# design.net
KiCad netlist of a schematic drawn in EAGLE
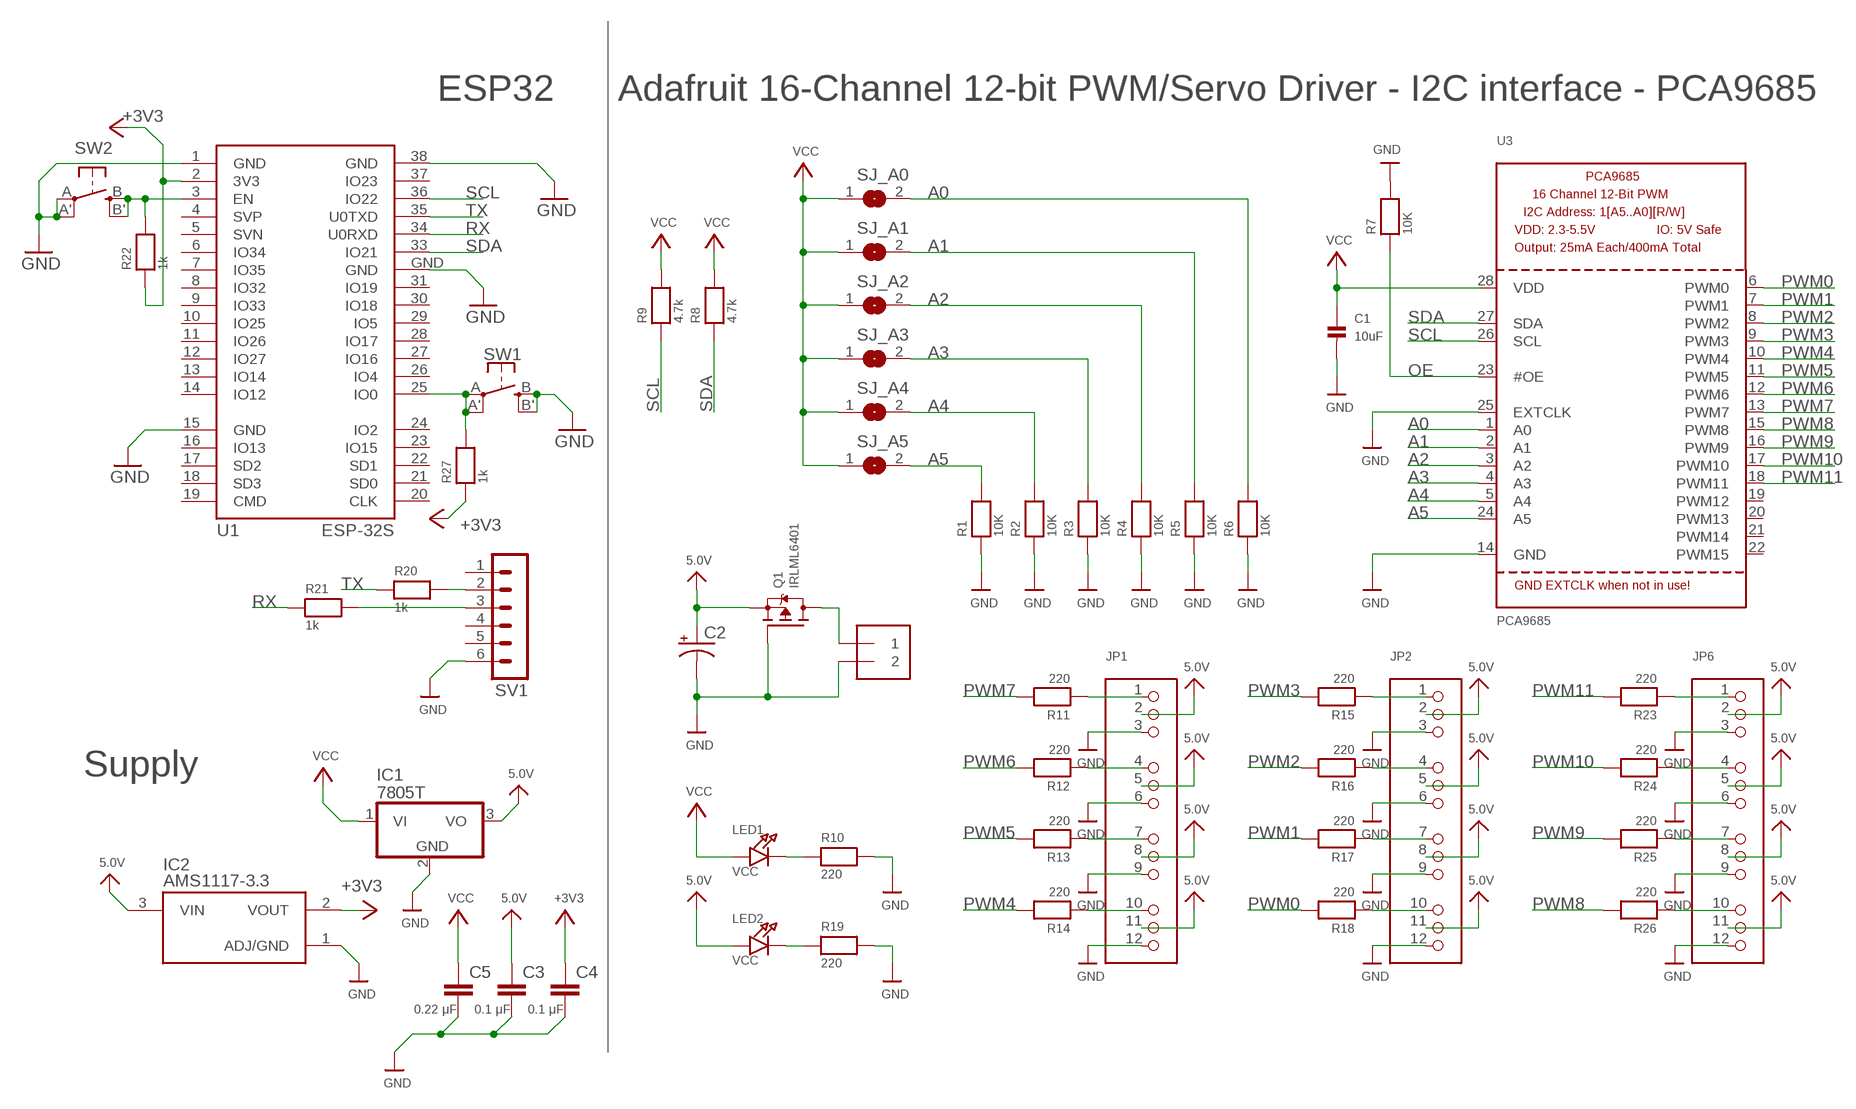
[diagram p0: schematic, sheet 1]

(export (version "E")
  (design (tool "Eeschema 10.0.6"))
  (components
    (comp (ref "C1")
      (value "10uF")
      (footprint "eagle-import:0805")
      (libsource (lib "eagle-import") (part "CAP_CERAMIC0805"))
    )
    (comp (ref "C2")
      (value "CPOL-USE3.5-8")
      (footprint "eagle-import:E3,5-8")
      (libsource (lib "eagle-import") (part "CPOL-USE3.5-8"))
    )
    (comp (ref "C3")
      (value "0.1 μF")
      (footprint "eagle-import:C2.5-2")
      (libsource (lib "eagle-import") (part "C2.5/2"))
    )
    (comp (ref "C4")
      (value "0.1 μF")
      (footprint "eagle-import:C2.5-2")
      (libsource (lib "eagle-import") (part "C2.5/2"))
    )
    (comp (ref "C5")
      (value "0.22 μF")
      (footprint "eagle-import:C2.5-2")
      (libsource (lib "eagle-import") (part "C2.5/2"))
    )
    (comp (ref "IC1")
      (value "7805T")
      (footprint "eagle-import:TO220H")
      (libsource (lib "eagle-import") (part "78T05"))
    )
    (comp (ref "IC2")
      (value "AMS1117-3.3")
      (footprint "eagle-import:SOT229P700X180-4N")
      (libsource (lib "eagle-import") (part "AMS1117-3.3"))
    )
    (comp (ref "J1")
      (value "TERMBLOCK_1X2-3.5MM")
      (footprint "eagle-import:1X2-3.5MM")
      (libsource (lib "eagle-import") (part "TERMBLOCK_1X2-3.5MM"))
    )
    (comp (ref "JP1")
      (value "HEADER-3X04")
      (footprint "eagle-import:3X04")
      (libsource (lib "eagle-import") (part "HEADER-3X04"))
    )
    (comp (ref "JP2")
      (value "HEADER-3X04")
      (footprint "eagle-import:3X04")
      (libsource (lib "eagle-import") (part "HEADER-3X04"))
    )
    (comp (ref "JP6")
      (value "HEADER-3X04")
      (footprint "eagle-import:3X04")
      (libsource (lib "eagle-import") (part "HEADER-3X04"))
    )
    (comp (ref "LED1")
      (value "VCC")
      (footprint "eagle-import:CHIPLED_0805")
      (libsource (lib "eagle-import") (part "LED0805"))
    )
    (comp (ref "LED2")
      (value "VCC")
      (footprint "eagle-import:CHIPLED_0805")
      (libsource (lib "eagle-import") (part "LED0805"))
    )
    (comp (ref "Q1")
      (value "IRLML6401")
      (footprint "eagle-import:SOT23-WIDE")
      (libsource (lib "eagle-import") (part "MOSFET-PWIDE"))
    )
    (comp (ref "R1")
      (value "10K")
      (footprint "eagle-import:0805")
      (libsource (lib "eagle-import") (part "RESISTOR0805"))
    )
    (comp (ref "R2")
      (value "10K")
      (footprint "eagle-import:0805")
      (libsource (lib "eagle-import") (part "RESISTOR0805"))
    )
    (comp (ref "R3")
      (value "10K")
      (footprint "eagle-import:0805")
      (libsource (lib "eagle-import") (part "RESISTOR0805"))
    )
    (comp (ref "R4")
      (value "10K")
      (footprint "eagle-import:0805")
      (libsource (lib "eagle-import") (part "RESISTOR0805"))
    )
    (comp (ref "R5")
      (value "10K")
      (footprint "eagle-import:0805")
      (libsource (lib "eagle-import") (part "RESISTOR0805"))
    )
    (comp (ref "R6")
      (value "10K")
      (footprint "eagle-import:0805")
      (libsource (lib "eagle-import") (part "RESISTOR0805"))
    )
    (comp (ref "R7")
      (value "10K")
      (footprint "eagle-import:0805")
      (libsource (lib "eagle-import") (part "RESISTOR0805"))
    )
    (comp (ref "R8")
      (value "4.7k")
      (footprint "eagle-import:0805")
      (libsource (lib "eagle-import") (part "RESISTOR0805"))
    )
    (comp (ref "R9")
      (value "4.7k")
      (footprint "eagle-import:0805")
      (libsource (lib "eagle-import") (part "RESISTOR0805"))
    )
    (comp (ref "R10")
      (value "220")
      (footprint "eagle-import:0805")
      (libsource (lib "eagle-import") (part "RESISTOR0805"))
    )
    (comp (ref "R11")
      (value "220")
      (footprint "eagle-import:0805")
      (libsource (lib "eagle-import") (part "RESISTOR0805"))
    )
    (comp (ref "R12")
      (value "220")
      (footprint "eagle-import:0805")
      (libsource (lib "eagle-import") (part "RESISTOR0805"))
    )
    (comp (ref "R13")
      (value "220")
      (footprint "eagle-import:0805")
      (libsource (lib "eagle-import") (part "RESISTOR0805"))
    )
    (comp (ref "R14")
      (value "220")
      (footprint "eagle-import:0805")
      (libsource (lib "eagle-import") (part "RESISTOR0805"))
    )
    (comp (ref "R15")
      (value "220")
      (footprint "eagle-import:0805")
      (libsource (lib "eagle-import") (part "RESISTOR0805"))
    )
    (comp (ref "R16")
      (value "220")
      (footprint "eagle-import:0805")
      (libsource (lib "eagle-import") (part "RESISTOR0805"))
    )
    (comp (ref "R17")
      (value "220")
      (footprint "eagle-import:0805")
      (libsource (lib "eagle-import") (part "RESISTOR0805"))
    )
    (comp (ref "R18")
      (value "220")
      (footprint "eagle-import:0805")
      (libsource (lib "eagle-import") (part "RESISTOR0805"))
    )
    (comp (ref "R19")
      (value "220")
      (footprint "eagle-import:0805")
      (libsource (lib "eagle-import") (part "RESISTOR0805"))
    )
    (comp (ref "R20")
      (value "1k")
      (footprint "eagle-import:0805")
      (libsource (lib "eagle-import") (part "RESISTOR0805"))
    )
    (comp (ref "R21")
      (value "1k")
      (footprint "eagle-import:0805")
      (libsource (lib "eagle-import") (part "RESISTOR0805"))
    )
    (comp (ref "R22")
      (value "1k")
      (footprint "eagle-import:0805")
      (libsource (lib "eagle-import") (part "RESISTOR0805"))
    )
    (comp (ref "R23")
      (value "220")
      (footprint "eagle-import:0805")
      (libsource (lib "eagle-import") (part "RESISTOR0805"))
    )
    (comp (ref "R24")
      (value "220")
      (footprint "eagle-import:0805")
      (libsource (lib "eagle-import") (part "RESISTOR0805"))
    )
    (comp (ref "R25")
      (value "220")
      (footprint "eagle-import:0805")
      (libsource (lib "eagle-import") (part "RESISTOR0805"))
    )
    (comp (ref "R26")
      (value "220")
      (footprint "eagle-import:0805")
      (libsource (lib "eagle-import") (part "RESISTOR0805"))
    )
    (comp (ref "R27")
      (value "1k")
      (footprint "eagle-import:0805")
      (libsource (lib "eagle-import") (part "RESISTOR0805"))
    )
    (comp (ref "SJ_A0")
      (value "SOLDERJUMPERREFLOW_NOPASTE")
      (footprint "eagle-import:SOLDERJUMPER_REFLOW_NOPASTE")
      (libsource (lib "eagle-import") (part "SOLDERJUMPERREFLOW_NOPASTE"))
    )
    (comp (ref "SJ_A1")
      (value "SOLDERJUMPERREFLOW_NOPASTE")
      (footprint "eagle-import:SOLDERJUMPER_REFLOW_NOPASTE")
      (libsource (lib "eagle-import") (part "SOLDERJUMPERREFLOW_NOPASTE"))
    )
    (comp (ref "SJ_A2")
      (value "SOLDERJUMPERREFLOW_NOPASTE")
      (footprint "eagle-import:SOLDERJUMPER_REFLOW_NOPASTE")
      (libsource (lib "eagle-import") (part "SOLDERJUMPERREFLOW_NOPASTE"))
    )
    (comp (ref "SJ_A3")
      (value "SOLDERJUMPERREFLOW_NOPASTE")
      (footprint "eagle-import:SOLDERJUMPER_REFLOW_NOPASTE")
      (libsource (lib "eagle-import") (part "SOLDERJUMPERREFLOW_NOPASTE"))
    )
    (comp (ref "SJ_A4")
      (value "SOLDERJUMPERREFLOW_NOPASTE")
      (footprint "eagle-import:SOLDERJUMPER_REFLOW_NOPASTE")
      (libsource (lib "eagle-import") (part "SOLDERJUMPERREFLOW_NOPASTE"))
    )
    (comp (ref "SJ_A5")
      (value "SOLDERJUMPERREFLOW_NOPASTE")
      (footprint "eagle-import:SOLDERJUMPER_REFLOW_NOPASTE")
      (libsource (lib "eagle-import") (part "SOLDERJUMPERREFLOW_NOPASTE"))
    )
    (comp (ref "SV1")
      (value "MA06-1")
      (footprint "eagle-import:MA06-1")
      (libsource (lib "eagle-import") (part "MA06-1"))
    )
    (comp (ref "SW1")
      (value "SPST_TACT-EVQQ2")
      (footprint "eagle-import:EVQ-Q2")
      (libsource (lib "eagle-import") (part "SPST_TACT-EVQQ2"))
    )
    (comp (ref "SW2")
      (value "SPST_TACT-EVQQ2")
      (footprint "eagle-import:EVQ-Q2")
      (libsource (lib "eagle-import") (part "SPST_TACT-EVQQ2"))
    )
    (comp (ref "U1")
      (value "ESP-32S")
      (footprint "eagle-import:ESP-32S")
      (libsource (lib "eagle-import") (part "ESP-32S"))
    )
    (comp (ref "U3")
      (value "PCA9685")
      (footprint "eagle-import:TSSOP28")
      (libsource (lib "eagle-import") (part "PCA9685"))
    )
  )
  (nets
    (net (code "1") (name "+3V3") (class "Default")
      (node (ref "C4") (pin "1") (pinfunction "1_1") (pintype "passive"))
      (node (ref "IC2") (pin "2") (pinfunction "VOUT_2") (pintype "output"))
      (node (ref "R22") (pin "1") (pinfunction "1_1") (pintype "passive"))
      (node (ref "R27") (pin "1") (pinfunction "1_1") (pintype "passive"))
      (node (ref "U1") (pin "2") (pinfunction "3V3_2") (pintype "power_in"))
    )
    (net (code "2") (name "/A0") (class "Default")
      (node (ref "R6") (pin "2") (pinfunction "2_2") (pintype "passive"))
      (node (ref "SJ_A0") (pin "2") (pinfunction "2_2") (pintype "passive"))
      (node (ref "U3") (pin "1") (pinfunction "A0_1") (pintype "bidirectional"))
    )
    (net (code "3") (name "/A1") (class "Default")
      (node (ref "R5") (pin "2") (pinfunction "2_2") (pintype "passive"))
      (node (ref "SJ_A1") (pin "2") (pinfunction "2_2") (pintype "passive"))
      (node (ref "U3") (pin "2") (pinfunction "A1_2") (pintype "bidirectional"))
    )
    (net (code "4") (name "/A2") (class "Default")
      (node (ref "R4") (pin "2") (pinfunction "2_2") (pintype "passive"))
      (node (ref "SJ_A2") (pin "2") (pinfunction "2_2") (pintype "passive"))
      (node (ref "U3") (pin "3") (pinfunction "A2_3") (pintype "bidirectional"))
    )
    (net (code "5") (name "/A3") (class "Default")
      (node (ref "R3") (pin "2") (pinfunction "2_2") (pintype "passive"))
      (node (ref "SJ_A3") (pin "2") (pinfunction "2_2") (pintype "passive"))
      (node (ref "U3") (pin "4") (pinfunction "A3_4") (pintype "bidirectional"))
    )
    (net (code "6") (name "/A4") (class "Default")
      (node (ref "R2") (pin "2") (pinfunction "2_2") (pintype "passive"))
      (node (ref "SJ_A4") (pin "2") (pinfunction "2_2") (pintype "passive"))
      (node (ref "U3") (pin "5") (pinfunction "A4_5") (pintype "bidirectional"))
    )
    (net (code "7") (name "/A5") (class "Default")
      (node (ref "R1") (pin "2") (pinfunction "2_2") (pintype "passive"))
      (node (ref "SJ_A5") (pin "2") (pinfunction "2_2") (pintype "passive"))
      (node (ref "U3") (pin "24") (pinfunction "A5_24") (pintype "bidirectional"))
    )
    (net (code "8") (name "/OE") (class "Default")
      (node (ref "R7") (pin "1") (pinfunction "1_1") (pintype "passive"))
      (node (ref "U3") (pin "23") (pinfunction "#OE_23") (pintype "input"))
    )
    (net (code "9") (name "/PWM0") (class "Default")
      (node (ref "R18") (pin "2") (pinfunction "2_2") (pintype "passive"))
      (node (ref "U3") (pin "6") (pinfunction "PWM0_6") (pintype "output"))
    )
    (net (code "10") (name "/PWM1") (class "Default")
      (node (ref "R17") (pin "2") (pinfunction "2_2") (pintype "passive"))
      (node (ref "U3") (pin "7") (pinfunction "PWM1_7") (pintype "output"))
    )
    (net (code "11") (name "/PWM2") (class "Default")
      (node (ref "R16") (pin "2") (pinfunction "2_2") (pintype "passive"))
      (node (ref "U3") (pin "8") (pinfunction "PWM2_8") (pintype "output"))
    )
    (net (code "12") (name "/PWM3") (class "Default")
      (node (ref "R15") (pin "2") (pinfunction "2_2") (pintype "passive"))
      (node (ref "U3") (pin "9") (pinfunction "PWM3_9") (pintype "output"))
    )
    (net (code "13") (name "/PWM4") (class "Default")
      (node (ref "R14") (pin "2") (pinfunction "2_2") (pintype "passive"))
      (node (ref "U3") (pin "10") (pinfunction "PWM4_10") (pintype "output"))
    )
    (net (code "14") (name "/PWM5") (class "Default")
      (node (ref "R13") (pin "2") (pinfunction "2_2") (pintype "passive"))
      (node (ref "U3") (pin "11") (pinfunction "PWM5_11") (pintype "output"))
    )
    (net (code "15") (name "/PWM6") (class "Default")
      (node (ref "R12") (pin "2") (pinfunction "2_2") (pintype "passive"))
      (node (ref "U3") (pin "12") (pinfunction "PWM6_12") (pintype "output"))
    )
    (net (code "16") (name "/PWM7") (class "Default")
      (node (ref "R11") (pin "2") (pinfunction "2_2") (pintype "passive"))
      (node (ref "U3") (pin "13") (pinfunction "PWM7_13") (pintype "output"))
    )
    (net (code "17") (name "/PWM8") (class "Default")
      (node (ref "R26") (pin "2") (pinfunction "2_2") (pintype "passive"))
      (node (ref "U3") (pin "15") (pinfunction "PWM8_15") (pintype "output"))
    )
    (net (code "18") (name "/PWM9") (class "Default")
      (node (ref "R25") (pin "2") (pinfunction "2_2") (pintype "passive"))
      (node (ref "U3") (pin "16") (pinfunction "PWM9_16") (pintype "output"))
    )
    (net (code "19") (name "/PWM10") (class "Default")
      (node (ref "R24") (pin "2") (pinfunction "2_2") (pintype "passive"))
      (node (ref "U3") (pin "17") (pinfunction "PWM10_17") (pintype "output"))
    )
    (net (code "20") (name "/PWM11") (class "Default")
      (node (ref "R23") (pin "2") (pinfunction "2_2") (pintype "passive"))
      (node (ref "U3") (pin "18") (pinfunction "PWM11_18") (pintype "output"))
    )
    (net (code "21") (name "/RX") (class "Default")
      (node (ref "R21") (pin "1") (pinfunction "1_1") (pintype "passive"))
      (node (ref "U1") (pin "34") (pinfunction "U0RXD_34") (pintype "bidirectional"))
    )
    (net (code "22") (name "/SCL") (class "Default")
      (node (ref "R9") (pin "1") (pinfunction "1_1") (pintype "passive"))
      (node (ref "U1") (pin "36") (pinfunction "IO22_36") (pintype "bidirectional"))
      (node (ref "U3") (pin "26") (pinfunction "SCL_26") (pintype "bidirectional"))
    )
    (net (code "23") (name "/SDA") (class "Default")
      (node (ref "R8") (pin "1") (pinfunction "1_1") (pintype "passive"))
      (node (ref "U1") (pin "33") (pinfunction "IO21_33") (pintype "bidirectional"))
      (node (ref "U3") (pin "27") (pinfunction "SDA_27") (pintype "bidirectional"))
    )
    (net (code "24") (name "/TX") (class "Default")
      (node (ref "R20") (pin "1") (pinfunction "1_1") (pintype "passive"))
      (node (ref "U1") (pin "35") (pinfunction "U0TXD_35") (pintype "bidirectional"))
    )
    (net (code "25") (name "5.0V") (class "Default")
      (node (ref "C2") (pin "+") (pinfunction "+_+") (pintype "passive"))
      (node (ref "C3") (pin "1") (pinfunction "1_1") (pintype "passive"))
      (node (ref "IC1") (pin "3") (pinfunction "VO_3") (pintype "passive"))
      (node (ref "IC2") (pin "3") (pinfunction "VIN_3") (pintype "input"))
      (node (ref "JP1") (pin "11") (pinfunction "11_11") (pintype "passive"))
      (node (ref "JP1") (pin "2") (pinfunction "2_2") (pintype "passive"))
      (node (ref "JP1") (pin "5") (pinfunction "5_5") (pintype "passive"))
      (node (ref "JP1") (pin "8") (pinfunction "8_8") (pintype "passive"))
      (node (ref "JP2") (pin "11") (pinfunction "11_11") (pintype "passive"))
      (node (ref "JP2") (pin "2") (pinfunction "2_2") (pintype "passive"))
      (node (ref "JP2") (pin "5") (pinfunction "5_5") (pintype "passive"))
      (node (ref "JP2") (pin "8") (pinfunction "8_8") (pintype "passive"))
      (node (ref "JP6") (pin "11") (pinfunction "11_11") (pintype "passive"))
      (node (ref "JP6") (pin "2") (pinfunction "2_2") (pintype "passive"))
      (node (ref "JP6") (pin "5") (pinfunction "5_5") (pintype "passive"))
      (node (ref "JP6") (pin "8") (pinfunction "8_8") (pintype "passive"))
      (node (ref "LED2") (pin "A") (pinfunction "A_A") (pintype "passive"))
      (node (ref "Q1") (pin "2") (pinfunction "S_2") (pintype "passive"))
    )
    (net (code "26") (name "GND") (class "Default")
      (node (ref "C1") (pin "2") (pinfunction "P$2_2") (pintype "passive"))
      (node (ref "C2") (pin "-") (pinfunction "-_-") (pintype "passive"))
      (node (ref "C3") (pin "2") (pinfunction "2_2") (pintype "passive"))
      (node (ref "C4") (pin "2") (pinfunction "2_2") (pintype "passive"))
      (node (ref "C5") (pin "2") (pinfunction "2_2") (pintype "passive"))
      (node (ref "IC1") (pin "2") (pinfunction "GND_2") (pintype "passive"))
      (node (ref "IC2") (pin "1") (pinfunction "ADJ/GND_1") (pintype "power_in"))
      (node (ref "J1") (pin "2") (pinfunction "2_2") (pintype "passive"))
      (node (ref "JP1") (pin "12") (pinfunction "12_12") (pintype "passive"))
      (node (ref "JP1") (pin "3") (pinfunction "3_3") (pintype "passive"))
      (node (ref "JP1") (pin "6") (pinfunction "6_6") (pintype "passive"))
      (node (ref "JP1") (pin "9") (pinfunction "9_9") (pintype "passive"))
      (node (ref "JP2") (pin "12") (pinfunction "12_12") (pintype "passive"))
      (node (ref "JP2") (pin "3") (pinfunction "3_3") (pintype "passive"))
      (node (ref "JP2") (pin "6") (pinfunction "6_6") (pintype "passive"))
      (node (ref "JP2") (pin "9") (pinfunction "9_9") (pintype "passive"))
      (node (ref "JP6") (pin "12") (pinfunction "12_12") (pintype "passive"))
      (node (ref "JP6") (pin "3") (pinfunction "3_3") (pintype "passive"))
      (node (ref "JP6") (pin "6") (pinfunction "6_6") (pintype "passive"))
      (node (ref "JP6") (pin "9") (pinfunction "9_9") (pintype "passive"))
      (node (ref "Q1") (pin "1") (pinfunction "G_1") (pintype "passive"))
      (node (ref "R1") (pin "1") (pinfunction "1_1") (pintype "passive"))
      (node (ref "R10") (pin "2") (pinfunction "2_2") (pintype "passive"))
      (node (ref "R19") (pin "2") (pinfunction "2_2") (pintype "passive"))
      (node (ref "R2") (pin "1") (pinfunction "1_1") (pintype "passive"))
      (node (ref "R3") (pin "1") (pinfunction "1_1") (pintype "passive"))
      (node (ref "R4") (pin "1") (pinfunction "1_1") (pintype "passive"))
      (node (ref "R5") (pin "1") (pinfunction "1_1") (pintype "passive"))
      (node (ref "R6") (pin "1") (pinfunction "1_1") (pintype "passive"))
      (node (ref "R7") (pin "2") (pinfunction "2_2") (pintype "passive"))
      (node (ref "SV1") (pin "6") (pinfunction "6_6") (pintype "passive"))
      (node (ref "SW1") (pin "B") (pinfunction "S_B") (pintype "passive"))
      (node (ref "SW1") (pin "B'") (pinfunction "S1_B'") (pintype "passive"))
      (node (ref "SW2") (pin "A") (pinfunction "P_A") (pintype "passive"))
      (node (ref "SW2") (pin "A'") (pinfunction "P1_A'") (pintype "passive"))
      (node (ref "U1") (pin "1") (pinfunction "GND_1") (pintype "power_in"))
      (node (ref "U1") (pin "15") (pinfunction "GND_15") (pintype "power_in"))
      (node (ref "U1") (pin "38") (pinfunction "GND_38") (pintype "power_in"))
      (node (ref "U1") (pin "GND") (pinfunction "GND_GND") (pintype "power_in"))
      (node (ref "U3") (pin "14") (pinfunction "GND_14") (pintype "power_in"))
      (node (ref "U3") (pin "25") (pinfunction "EXTCLK_25") (pintype "input"))
    )
    (net (code "27") (name "Net-(JP1-Pad1)") (class "Default")
      (node (ref "JP1") (pin "1") (pinfunction "1_1") (pintype "passive"))
      (node (ref "R11") (pin "1") (pinfunction "1_1") (pintype "passive"))
    )
    (net (code "28") (name "Net-(JP1-Pad4)") (class "Default")
      (node (ref "JP1") (pin "4") (pinfunction "4_4") (pintype "passive"))
      (node (ref "R12") (pin "1") (pinfunction "1_1") (pintype "passive"))
    )
    (net (code "29") (name "Net-(JP1-Pad7)") (class "Default")
      (node (ref "JP1") (pin "7") (pinfunction "7_7") (pintype "passive"))
      (node (ref "R13") (pin "1") (pinfunction "1_1") (pintype "passive"))
    )
    (net (code "30") (name "Net-(JP1-Pad10)") (class "Default")
      (node (ref "JP1") (pin "10") (pinfunction "10_10") (pintype "passive"))
      (node (ref "R14") (pin "1") (pinfunction "1_1") (pintype "passive"))
    )
    (net (code "31") (name "Net-(JP2-Pad1)") (class "Default")
      (node (ref "JP2") (pin "1") (pinfunction "1_1") (pintype "passive"))
      (node (ref "R15") (pin "1") (pinfunction "1_1") (pintype "passive"))
    )
    (net (code "32") (name "Net-(JP2-Pad4)") (class "Default")
      (node (ref "JP2") (pin "4") (pinfunction "4_4") (pintype "passive"))
      (node (ref "R16") (pin "1") (pinfunction "1_1") (pintype "passive"))
    )
    (net (code "33") (name "Net-(JP2-Pad7)") (class "Default")
      (node (ref "JP2") (pin "7") (pinfunction "7_7") (pintype "passive"))
      (node (ref "R17") (pin "1") (pinfunction "1_1") (pintype "passive"))
    )
    (net (code "34") (name "Net-(JP2-Pad10)") (class "Default")
      (node (ref "JP2") (pin "10") (pinfunction "10_10") (pintype "passive"))
      (node (ref "R18") (pin "1") (pinfunction "1_1") (pintype "passive"))
    )
    (net (code "35") (name "Net-(JP6-Pad1)") (class "Default")
      (node (ref "JP6") (pin "1") (pinfunction "1_1") (pintype "passive"))
      (node (ref "R23") (pin "1") (pinfunction "1_1") (pintype "passive"))
    )
    (net (code "36") (name "Net-(JP6-Pad4)") (class "Default")
      (node (ref "JP6") (pin "4") (pinfunction "4_4") (pintype "passive"))
      (node (ref "R24") (pin "1") (pinfunction "1_1") (pintype "passive"))
    )
    (net (code "37") (name "Net-(JP6-Pad7)") (class "Default")
      (node (ref "JP6") (pin "7") (pinfunction "7_7") (pintype "passive"))
      (node (ref "R25") (pin "1") (pinfunction "1_1") (pintype "passive"))
    )
    (net (code "38") (name "Net-(JP6-Pad10)") (class "Default")
      (node (ref "JP6") (pin "10") (pinfunction "10_10") (pintype "passive"))
      (node (ref "R26") (pin "1") (pinfunction "1_1") (pintype "passive"))
    )
    (net (code "39") (name "Net-(LED1-PadC)") (class "Default")
      (node (ref "LED1") (pin "C") (pinfunction "C_C") (pintype "passive"))
      (node (ref "R10") (pin "1") (pinfunction "1_1") (pintype "passive"))
    )
    (net (code "40") (name "Net-(LED2-PadC)") (class "Default")
      (node (ref "LED2") (pin "C") (pinfunction "C_C") (pintype "passive"))
      (node (ref "R19") (pin "1") (pinfunction "1_1") (pintype "passive"))
    )
    (net (code "41") (name "Net-(Q1-D)") (class "Default")
      (node (ref "J1") (pin "1") (pinfunction "1_1") (pintype "passive"))
      (node (ref "Q1") (pin "3") (pinfunction "D_3") (pintype "passive"))
    )
    (net (code "42") (name "Net-(R20-Pad2)") (class "Default")
      (node (ref "R20") (pin "2") (pinfunction "2_2") (pintype "passive"))
      (node (ref "SV1") (pin "2") (pinfunction "2_2") (pintype "passive"))
    )
    (net (code "43") (name "Net-(R21-Pad2)") (class "Default")
      (node (ref "R21") (pin "2") (pinfunction "2_2") (pintype "passive"))
      (node (ref "SV1") (pin "3") (pinfunction "3_3") (pintype "passive"))
    )
    (net (code "44") (name "Net-(SW1-P)") (class "Default")
      (node (ref "R27") (pin "2") (pinfunction "2_2") (pintype "passive"))
      (node (ref "SW1") (pin "A") (pinfunction "P_A") (pintype "passive"))
      (node (ref "SW1") (pin "A'") (pinfunction "P1_A'") (pintype "passive"))
      (node (ref "U1") (pin "25") (pinfunction "IO0_25") (pintype "bidirectional"))
    )
    (net (code "45") (name "Net-(SW2-S)") (class "Default")
      (node (ref "R22") (pin "2") (pinfunction "2_2") (pintype "passive"))
      (node (ref "SW2") (pin "B") (pinfunction "S_B") (pintype "passive"))
      (node (ref "SW2") (pin "B'") (pinfunction "S1_B'") (pintype "passive"))
      (node (ref "U1") (pin "3") (pinfunction "EN_3") (pintype "input"))
    )
    (net (code "46") (name "VCC") (class "Default")
      (node (ref "C1") (pin "1") (pinfunction "P$1_1") (pintype "passive"))
      (node (ref "C5") (pin "1") (pinfunction "1_1") (pintype "passive"))
      (node (ref "IC1") (pin "1") (pinfunction "VI_1") (pintype "input"))
      (node (ref "LED1") (pin "A") (pinfunction "A_A") (pintype "passive"))
      (node (ref "R8") (pin "2") (pinfunction "2_2") (pintype "passive"))
      (node (ref "R9") (pin "2") (pinfunction "2_2") (pintype "passive"))
      (node (ref "SJ_A0") (pin "1") (pinfunction "1_1") (pintype "passive"))
      (node (ref "SJ_A1") (pin "1") (pinfunction "1_1") (pintype "passive"))
      (node (ref "SJ_A2") (pin "1") (pinfunction "1_1") (pintype "passive"))
      (node (ref "SJ_A3") (pin "1") (pinfunction "1_1") (pintype "passive"))
      (node (ref "SJ_A4") (pin "1") (pinfunction "1_1") (pintype "passive"))
      (node (ref "SJ_A5") (pin "1") (pinfunction "1_1") (pintype "passive"))
      (node (ref "U3") (pin "28") (pinfunction "VDD_28") (pintype "power_in"))
    )
    (net (code "47") (name "unconnected-(SV1-Pad1)") (class "Default")
      (node (ref "SV1") (pin "1") (pinfunction "1_1") (pintype "passive"))
    )
    (net (code "48") (name "unconnected-(SV1-Pad4)") (class "Default")
      (node (ref "SV1") (pin "4") (pinfunction "4_4") (pintype "passive"))
    )
    (net (code "49") (name "unconnected-(SV1-Pad5)") (class "Default")
      (node (ref "SV1") (pin "5") (pinfunction "5_5") (pintype "passive"))
    )
    (net (code "50") (name "unconnected-(U1-CLK-Pad20)") (class "Default")
      (node (ref "U1") (pin "20") (pinfunction "CLK_20") (pintype "bidirectional"))
    )
    (net (code "51") (name "unconnected-(U1-CMD-Pad19)") (class "Default")
      (node (ref "U1") (pin "19") (pinfunction "CMD_19") (pintype "bidirectional"))
    )
    (net (code "52") (name "unconnected-(U1-IO2-Pad24)") (class "Default")
      (node (ref "U1") (pin "24") (pinfunction "IO2_24") (pintype "bidirectional"))
    )
    (net (code "53") (name "unconnected-(U1-IO4-Pad26)") (class "Default")
      (node (ref "U1") (pin "26") (pinfunction "IO4_26") (pintype "bidirectional"))
    )
    (net (code "54") (name "unconnected-(U1-IO5-Pad29)") (class "Default")
      (node (ref "U1") (pin "29") (pinfunction "IO5_29") (pintype "bidirectional"))
    )
    (net (code "55") (name "unconnected-(U1-IO12-Pad14)") (class "Default")
      (node (ref "U1") (pin "14") (pinfunction "IO12_14") (pintype "bidirectional"))
    )
    (net (code "56") (name "unconnected-(U1-IO13-Pad16)") (class "Default")
      (node (ref "U1") (pin "16") (pinfunction "IO13_16") (pintype "bidirectional"))
    )
    (net (code "57") (name "unconnected-(U1-IO14-Pad13)") (class "Default")
      (node (ref "U1") (pin "13") (pinfunction "IO14_13") (pintype "bidirectional"))
    )
    (net (code "58") (name "unconnected-(U1-IO15-Pad23)") (class "Default")
      (node (ref "U1") (pin "23") (pinfunction "IO15_23") (pintype "bidirectional"))
    )
    (net (code "59") (name "unconnected-(U1-IO16-Pad27)") (class "Default")
      (node (ref "U1") (pin "27") (pinfunction "IO16_27") (pintype "bidirectional"))
    )
    (net (code "60") (name "unconnected-(U1-IO17-Pad28)") (class "Default")
      (node (ref "U1") (pin "28") (pinfunction "IO17_28") (pintype "bidirectional"))
    )
    (net (code "61") (name "unconnected-(U1-IO18-Pad30)") (class "Default")
      (node (ref "U1") (pin "30") (pinfunction "IO18_30") (pintype "bidirectional"))
    )
    (net (code "62") (name "unconnected-(U1-IO19-Pad31)") (class "Default")
      (node (ref "U1") (pin "31") (pinfunction "IO19_31") (pintype "bidirectional"))
    )
    (net (code "63") (name "unconnected-(U1-IO23-Pad37)") (class "Default")
      (node (ref "U1") (pin "37") (pinfunction "IO23_37") (pintype "bidirectional"))
    )
    (net (code "64") (name "unconnected-(U1-IO25-Pad10)") (class "Default")
      (node (ref "U1") (pin "10") (pinfunction "IO25_10") (pintype "bidirectional"))
    )
    (net (code "65") (name "unconnected-(U1-IO26-Pad11)") (class "Default")
      (node (ref "U1") (pin "11") (pinfunction "IO26_11") (pintype "bidirectional"))
    )
    (net (code "66") (name "unconnected-(U1-IO27-Pad12)") (class "Default")
      (node (ref "U1") (pin "12") (pinfunction "IO27_12") (pintype "bidirectional"))
    )
    (net (code "67") (name "unconnected-(U1-IO32-Pad8)") (class "Default")
      (node (ref "U1") (pin "8") (pinfunction "IO32_8") (pintype "bidirectional"))
    )
    (net (code "68") (name "unconnected-(U1-IO33-Pad9)") (class "Default")
      (node (ref "U1") (pin "9") (pinfunction "IO33_9") (pintype "bidirectional"))
    )
    (net (code "69") (name "unconnected-(U1-IO34-Pad6)") (class "Default")
      (node (ref "U1") (pin "6") (pinfunction "IO34_6") (pintype "bidirectional"))
    )
    (net (code "70") (name "unconnected-(U1-IO35-Pad7)") (class "Default")
      (node (ref "U1") (pin "7") (pinfunction "IO35_7") (pintype "bidirectional"))
    )
    (net (code "71") (name "unconnected-(U1-SD0-Pad21)") (class "Default")
      (node (ref "U1") (pin "21") (pinfunction "SD0_21") (pintype "bidirectional"))
    )
    (net (code "72") (name "unconnected-(U1-SD1-Pad22)") (class "Default")
      (node (ref "U1") (pin "22") (pinfunction "SD1_22") (pintype "bidirectional"))
    )
    (net (code "73") (name "unconnected-(U1-SD2-Pad17)") (class "Default")
      (node (ref "U1") (pin "17") (pinfunction "SD2_17") (pintype "bidirectional"))
    )
    (net (code "74") (name "unconnected-(U1-SD3-Pad18)") (class "Default")
      (node (ref "U1") (pin "18") (pinfunction "SD3_18") (pintype "bidirectional"))
    )
    (net (code "75") (name "unconnected-(U1-SVN-Pad5)") (class "Default")
      (node (ref "U1") (pin "5") (pinfunction "SVN_5") (pintype "bidirectional"))
    )
    (net (code "76") (name "unconnected-(U1-SVP-Pad4)") (class "Default")
      (node (ref "U1") (pin "4") (pinfunction "SVP_4") (pintype "bidirectional"))
    )
    (net (code "77") (name "unconnected-(U3-PWM12-Pad19)") (class "Default")
      (node (ref "U3") (pin "19") (pinfunction "PWM12_19") (pintype "output"))
    )
    (net (code "78") (name "unconnected-(U3-PWM13-Pad20)") (class "Default")
      (node (ref "U3") (pin "20") (pinfunction "PWM13_20") (pintype "output"))
    )
    (net (code "79") (name "unconnected-(U3-PWM14-Pad21)") (class "Default")
      (node (ref "U3") (pin "21") (pinfunction "PWM14_21") (pintype "output"))
    )
    (net (code "80") (name "unconnected-(U3-PWM15-Pad22)") (class "Default")
      (node (ref "U3") (pin "22") (pinfunction "PWM15_22") (pintype "output"))
    )
  )
)
